# ESP32.net
KiCad netlist of a schematic drawn in Altium Designer
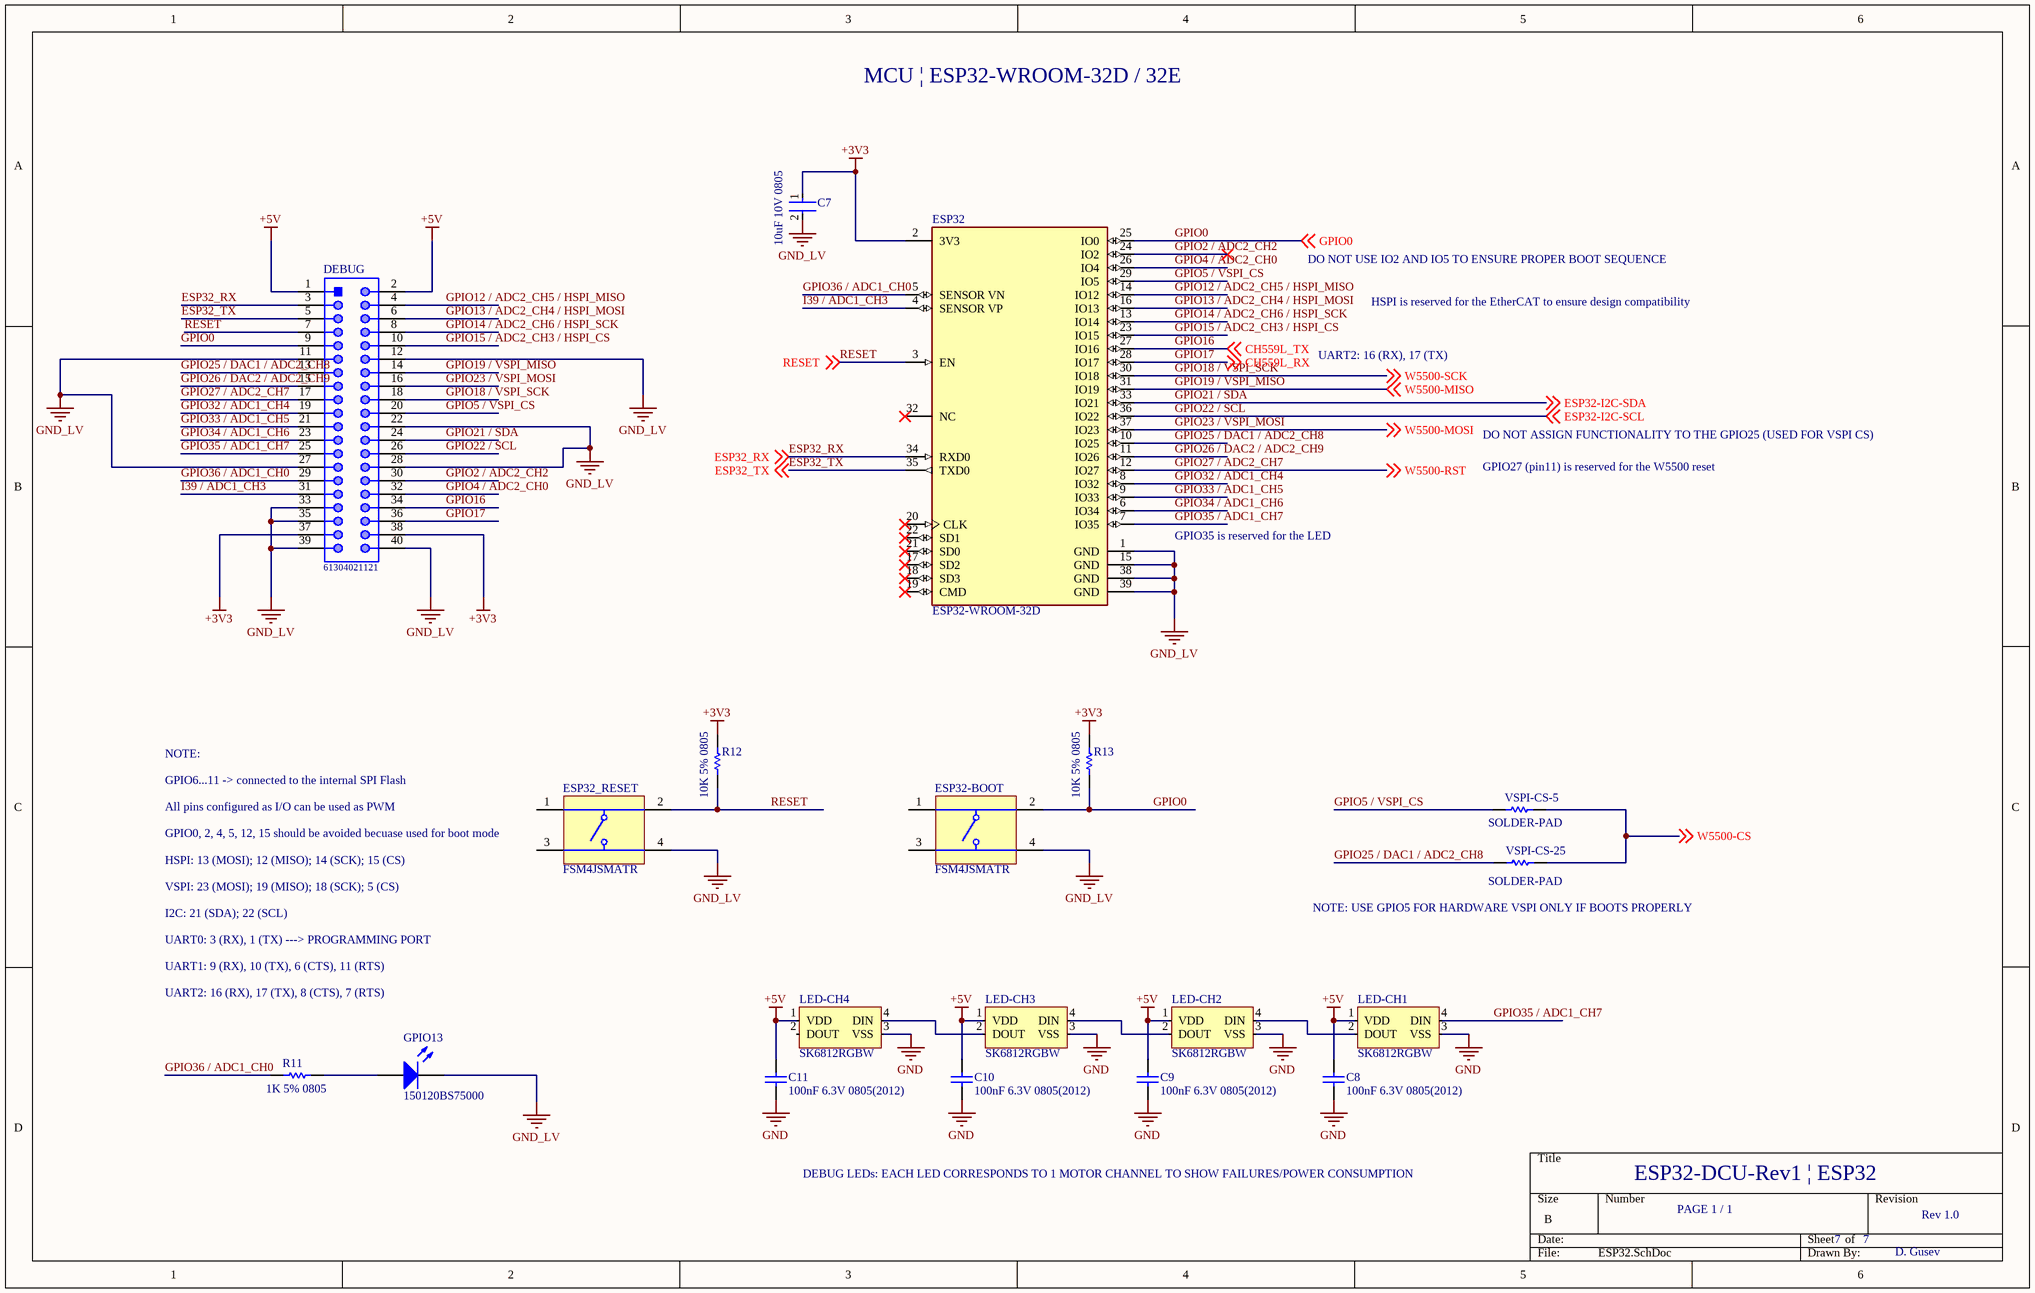
[diagram p0: ESP32.SchDoc]

(export (version "E")
  (design (tool "Eeschema 10.0.6"))
  (components
    (comp (ref "C7")
      (value "10uF 10V 0805")
      (footprint "FP-C0805C-DG-MFG")
      (description "CAP CER 10UF 10V X5R 0805")
      (fields (field (name "TOLERANCE") "10%") (field (name "MANUFACTURER PART NUMBER") "C0805C106K8PACTU"))
      (libsource (lib "Altium Content Vault") (part "11868f565c42a9108669ba33697ecf6"))
    )
    (comp (ref "C8")
      (value "100nF 6.3V 0805(2012)")
      (footprint "CAPC0805(2012)100_N")
      (description "CAP 100nF 6.3V ±20% 0805 (2012 Metric) Thickness 1mm SMD")
      (fields (field (name "TOLERANCE") "Â±20%"))
      (libsource (lib "Altium Content Vault") (part "CAP"))
    )
    (comp (ref "C9")
      (value "100nF 6.3V 0805(2012)")
      (footprint "CAPC0805(2012)100_N")
      (description "CAP 100nF 6.3V ±20% 0805 (2012 Metric) Thickness 1mm SMD")
      (fields (field (name "TOLERANCE") "Â±20%"))
      (libsource (lib "Altium Content Vault") (part "CAP"))
    )
    (comp (ref "C10")
      (value "100nF 6.3V 0805(2012)")
      (footprint "CAPC0805(2012)100_N")
      (description "CAP 100nF 6.3V ±20% 0805 (2012 Metric) Thickness 1mm SMD")
      (fields (field (name "TOLERANCE") "Â±20%"))
      (libsource (lib "Altium Content Vault") (part "CAP"))
    )
    (comp (ref "C11")
      (value "100nF 6.3V 0805(2012)")
      (footprint "CAPC0805(2012)100_N")
      (description "CAP 100nF 6.3V ±20% 0805 (2012 Metric) Thickness 1mm SMD")
      (fields (field (name "TOLERANCE") "Â±20%"))
      (libsource (lib "Altium Content Vault") (part "CAP"))
    )
    (comp (ref "DEBUG")
      (value "61304021121")
      (footprint "61304021121")
      (description "THT Vertical Pin Header WR-PHD, Pitch 2.54 mm, Dual Row, 40 pins")
      (fields (field (name "MANUFACTURER") "Wurth Elektronik") (field (name "PUBLISHER") "WurthElektronik"))
      (libsource (lib "Altium Content Vault") (part "WE-CN-2P-M-R40"))
    )
    (comp (ref "ESP32")
      (value "ESP32-WROOM-32D")
      (footprint "FP-ESP32-WROOM-32D-MFG")
      (description "WIFI MODULE 32MBITS SPI FLASH")
      (fields
        (field (name "OCTOPART") "https://octopart.com/esp32-wroom-32d-espressif+systems-91040050")
        (field (name "MANUFACTURER") "Espressif Systems")
      )
      (libsource (lib "Altium Content Vault") (part "a031a76f8c27026a7a7f4657ff233a3"))
    )
    (comp (ref "ESP32-BOOT")
      (value "FSM4JSMATR")
      (footprint "TECO-FSM4JSMATR_V")
      (description "Micro Miniature Push Button Switch FSM JSM, 50 mA, -35 to 85 degC, 4-Pin SMD, RoHS, Tape and Reel")
      (fields (field (name "MANUFACTURER") "TE Connectivity"))
      (libsource (lib "Altium Content Vault") (part "SW-SPST-4_A"))
    )
    (comp (ref "ESP32_RESET")
      (value "FSM4JSMATR")
      (footprint "TECO-FSM4JSMATR_V")
      (description "Micro Miniature Push Button Switch FSM JSM, 50 mA, -35 to 85 degC, 4-Pin SMD, RoHS, Tape and Reel")
      (fields (field (name "MANUFACTURER") "TE Connectivity"))
      (libsource (lib "Altium Content Vault") (part "SW-SPST-4_A"))
    )
    (comp (ref "GPIO13")
      (value "150120BS75000")
      (footprint "1206_A")
      (description "SMD mono-color Chip LED, WL-SMCW, Blue")
      (fields (field (name "MANUFACTURER") "Wuerth Elektronik"))
      (libsource (lib "Altium Content Vault") (part "WE-LED_K1A2-2"))
    )
    (comp (ref "LED-CH1")
      (value "SK6812RGBW")
      (footprint "SK6812RGBW")
      (libsource (lib "GT_YuYu") (part "SK6812RGBW"))
    )
    (comp (ref "LED-CH2")
      (value "SK6812RGBW")
      (footprint "SK6812RGBW")
      (libsource (lib "GT_YuYu") (part "SK6812RGBW"))
    )
    (comp (ref "LED-CH3")
      (value "SK6812RGBW")
      (footprint "SK6812RGBW")
      (libsource (lib "GT_YuYu") (part "SK6812RGBW"))
    )
    (comp (ref "LED-CH4")
      (value "SK6812RGBW")
      (footprint "SK6812RGBW")
      (libsource (lib "GT_YuYu") (part "SK6812RGBW"))
    )
    (comp (ref "R11")
      (value "1K 5% 0805")
      (footprint "RESC2013X60X40ML20T25")
      (fields (field (name "PART NUMBER") "ERA6AEB123V") (field (name "MANUFACTURER") "Panasonic"))
      (libsource (lib "Altium Content Vault") (part "RES"))
    )
    (comp (ref "R12")
      (value "10K 5% 0805")
      (footprint "RESC2013X60X40ML20T25")
      (fields (field (name "PART NUMBER") "ERA6AEB123V") (field (name "MANUFACTURER") "Panasonic"))
      (libsource (lib "Altium Content Vault") (part "RES"))
    )
    (comp (ref "R13")
      (value "10K 5% 0805")
      (footprint "RESC2013X60X40ML20T25")
      (fields (field (name "PART NUMBER") "ERA6AEB123V") (field (name "MANUFACTURER") "Panasonic"))
      (libsource (lib "Altium Content Vault") (part "RES"))
    )
    (comp (ref "VSPI-CS-5")
      (value "SOLDER-PAD")
      (footprint "RESC2013X60X35LL10T20")
      (description "Chip Resistor, 1 Ohm, +/- 1%, 125 mW, -55 to 155 degC, 0805 (2012 Metric), RoHS, Tape and Reel")
      (fields (field (name "MANUFACTURER") "Yageo"))
      (libsource (lib "Altium Content Vault") (part "RES-2"))
    )
    (comp (ref "VSPI-CS-25")
      (value "SOLDER-PAD")
      (footprint "RESC2013X60X35LL10T20")
      (description "Chip Resistor, 1 Ohm, +/- 1%, 125 mW, -55 to 155 degC, 0805 (2012 Metric), RoHS, Tape and Reel")
      (fields (field (name "MANUFACTURER") "Yageo"))
      (libsource (lib "Altium Content Vault") (part "RES-2"))
    )
  )
  (nets
    (net (code "1") (name "+3V3") (class "Default")
      (node (ref "C7") (pin "1") (pinfunction "1_1") (pintype "passive"))
      (node (ref "DEBUG") (pin "37") (pinfunction "37_37") (pintype "passive"))
      (node (ref "DEBUG") (pin "38") (pinfunction "38_38") (pintype "passive"))
      (node (ref "ESP32") (pin "2") (pinfunction "3V3_2") (pintype "power_in"))
      (node (ref "R12") (pin "2") (pinfunction "2_2") (pintype "passive"))
      (node (ref "R13") (pin "2") (pinfunction "2_2") (pintype "passive"))
    )
    (net (code "2") (name "+5V") (class "Default")
      (node (ref "C10") (pin "2") (pinfunction "2_2") (pintype "passive"))
      (node (ref "C11") (pin "2") (pinfunction "2_2") (pintype "passive"))
      (node (ref "C8") (pin "2") (pinfunction "2_2") (pintype "passive"))
      (node (ref "C9") (pin "2") (pinfunction "2_2") (pintype "passive"))
      (node (ref "DEBUG") (pin "1") (pinfunction "1_1") (pintype "passive"))
      (node (ref "DEBUG") (pin "2") (pinfunction "2_2") (pintype "passive"))
      (node (ref "LED-CH1") (pin "1") (pinfunction "VDD_1") (pintype "power_in"))
      (node (ref "LED-CH2") (pin "1") (pinfunction "VDD_1") (pintype "power_in"))
      (node (ref "LED-CH3") (pin "1") (pinfunction "VDD_1") (pintype "power_in"))
      (node (ref "LED-CH4") (pin "1") (pinfunction "VDD_1") (pintype "power_in"))
    )
    (net (code "3") (name "/GPIO2 {slash} ADC2_CH2") (class "Default")
      (node (ref "DEBUG") (pin "30") (pinfunction "30_30") (pintype "passive"))
      (node (ref "ESP32") (pin "24") (pinfunction "IO2_24") (pintype "bidirectional"))
    )
    (net (code "4") (name "/GPIO4 {slash} ADC2_CH0") (class "Default")
      (node (ref "DEBUG") (pin "32") (pinfunction "32_32") (pintype "passive"))
      (node (ref "ESP32") (pin "26") (pinfunction "IO4_26") (pintype "bidirectional"))
    )
    (net (code "5") (name "/GPIO5 {slash} VSPI_CS") (class "Default")
      (node (ref "DEBUG") (pin "20") (pinfunction "20_20") (pintype "passive"))
      (node (ref "ESP32") (pin "29") (pinfunction "IO5_29") (pintype "bidirectional"))
      (node (ref "VSPI-CS-5") (pin "1") (pinfunction "1_1") (pintype "passive"))
    )
    (net (code "6") (name "/GPIO12 {slash} ADC2_CH5 {slash} HSPI_MISO") (class "Default")
      (node (ref "DEBUG") (pin "4") (pinfunction "4_4") (pintype "passive"))
      (node (ref "ESP32") (pin "14") (pinfunction "IO12_14") (pintype "bidirectional"))
    )
    (net (code "7") (name "/GPIO13 {slash} ADC2_CH4 {slash} HSPI_MOSI") (class "Default")
      (node (ref "DEBUG") (pin "6") (pinfunction "6_6") (pintype "passive"))
      (node (ref "ESP32") (pin "16") (pinfunction "IO13_16") (pintype "bidirectional"))
    )
    (net (code "8") (name "/GPIO14 {slash} ADC2_CH6 {slash} HSPI_SCK") (class "Default")
      (node (ref "DEBUG") (pin "8") (pinfunction "8_8") (pintype "passive"))
      (node (ref "ESP32") (pin "13") (pinfunction "IO14_13") (pintype "bidirectional"))
    )
    (net (code "9") (name "/GPIO15 {slash} ADC2_CH3 {slash} HSPI_CS") (class "Default")
      (node (ref "DEBUG") (pin "10") (pinfunction "10_10") (pintype "passive"))
      (node (ref "ESP32") (pin "23") (pinfunction "IO15_23") (pintype "bidirectional"))
    )
    (net (code "10") (name "/GPIO25 {slash} DAC1 {slash} ADC2_CH8") (class "Default")
      (node (ref "DEBUG") (pin "13") (pinfunction "13_13") (pintype "passive"))
      (node (ref "ESP32") (pin "10") (pinfunction "IO25_10") (pintype "bidirectional"))
      (node (ref "VSPI-CS-25") (pin "1") (pinfunction "1_1") (pintype "passive"))
    )
    (net (code "11") (name "/GPIO26 {slash} DAC2 {slash} ADC2_CH9") (class "Default")
      (node (ref "DEBUG") (pin "15") (pinfunction "15_15") (pintype "passive"))
      (node (ref "ESP32") (pin "11") (pinfunction "IO26_11") (pintype "bidirectional"))
    )
    (net (code "12") (name "/GPIO32 {slash} ADC1_CH4") (class "Default")
      (node (ref "DEBUG") (pin "19") (pinfunction "19_19") (pintype "passive"))
      (node (ref "ESP32") (pin "8") (pinfunction "IO32_8") (pintype "bidirectional"))
    )
    (net (code "13") (name "/GPIO33 {slash} ADC1_CH5") (class "Default")
      (node (ref "DEBUG") (pin "21") (pinfunction "21_21") (pintype "passive"))
      (node (ref "ESP32") (pin "9") (pinfunction "IO33_9") (pintype "bidirectional"))
    )
    (net (code "14") (name "/GPIO34 {slash} ADC1_CH6") (class "Default")
      (node (ref "DEBUG") (pin "23") (pinfunction "23_23") (pintype "passive"))
      (node (ref "ESP32") (pin "6") (pinfunction "IO34_6") (pintype "bidirectional"))
    )
    (net (code "15") (name "/GPIO35 {slash} ADC1_CH7") (class "Default")
      (node (ref "DEBUG") (pin "25") (pinfunction "25_25") (pintype "passive"))
      (node (ref "ESP32") (pin "7") (pinfunction "IO35_7") (pintype "bidirectional"))
      (node (ref "LED-CH1") (pin "4") (pinfunction "DIN_4") (pintype "input"))
    )
    (net (code "16") (name "/GPIO36 {slash} ADC1_CH0") (class "Default")
      (node (ref "DEBUG") (pin "29") (pinfunction "29_29") (pintype "passive"))
      (node (ref "ESP32") (pin "5") (pinfunction "SENSOR_VN_5") (pintype "bidirectional"))
      (node (ref "R11") (pin "1") (pinfunction "1_1") (pintype "passive"))
    )
    (net (code "17") (name "/I39 {slash} ADC1_CH3") (class "Default")
      (node (ref "DEBUG") (pin "31") (pinfunction "31_31") (pintype "passive"))
      (node (ref "ESP32") (pin "4") (pinfunction "SENSOR_VP_4") (pintype "bidirectional"))
    )
    (net (code "18") (name "CH559L_RX") (class "Default")
      (node (ref "DEBUG") (pin "36") (pinfunction "36_36") (pintype "passive"))
      (node (ref "ESP32") (pin "28") (pinfunction "IO17_28") (pintype "bidirectional"))
    )
    (net (code "19") (name "CH559L_TX") (class "Default")
      (node (ref "DEBUG") (pin "34") (pinfunction "34_34") (pintype "passive"))
      (node (ref "ESP32") (pin "27") (pinfunction "IO16_27") (pintype "bidirectional"))
    )
    (net (code "20") (name "ESP32-I2C-SCL") (class "Default")
      (node (ref "DEBUG") (pin "26") (pinfunction "26_26") (pintype "passive"))
      (node (ref "ESP32") (pin "36") (pinfunction "IO22_36") (pintype "bidirectional"))
    )
    (net (code "21") (name "ESP32-I2C-SDA") (class "Default")
      (node (ref "DEBUG") (pin "24") (pinfunction "24_24") (pintype "passive"))
      (node (ref "ESP32") (pin "33") (pinfunction "IO21_33") (pintype "bidirectional"))
    )
    (net (code "22") (name "ESP32_RX") (class "Default")
      (node (ref "DEBUG") (pin "3") (pinfunction "3_3") (pintype "passive"))
      (node (ref "ESP32") (pin "34") (pinfunction "RXD0_34") (pintype "input"))
    )
    (net (code "23") (name "ESP32_TX") (class "Default")
      (node (ref "DEBUG") (pin "5") (pinfunction "5_5") (pintype "passive"))
      (node (ref "ESP32") (pin "35") (pinfunction "TXD0_35") (pintype "output"))
    )
    (net (code "24") (name "GND") (class "Default")
      (node (ref "C10") (pin "1") (pinfunction "1_1") (pintype "passive"))
      (node (ref "C11") (pin "1") (pinfunction "1_1") (pintype "passive"))
      (node (ref "C8") (pin "1") (pinfunction "1_1") (pintype "passive"))
      (node (ref "C9") (pin "1") (pinfunction "1_1") (pintype "passive"))
      (node (ref "LED-CH1") (pin "3") (pinfunction "VSS_3") (pintype "power_in"))
      (node (ref "LED-CH2") (pin "3") (pinfunction "VSS_3") (pintype "power_in"))
      (node (ref "LED-CH3") (pin "3") (pinfunction "VSS_3") (pintype "power_in"))
      (node (ref "LED-CH4") (pin "3") (pinfunction "VSS_3") (pintype "power_in"))
    )
    (net (code "25") (name "GND_LV") (class "Default")
      (node (ref "C7") (pin "2") (pinfunction "2_2") (pintype "passive"))
      (node (ref "DEBUG") (pin "11") (pinfunction "11_11") (pintype "passive"))
      (node (ref "DEBUG") (pin "12") (pinfunction "12_12") (pintype "passive"))
      (node (ref "DEBUG") (pin "22") (pinfunction "22_22") (pintype "passive"))
      (node (ref "DEBUG") (pin "27") (pinfunction "27_27") (pintype "passive"))
      (node (ref "DEBUG") (pin "28") (pinfunction "28_28") (pintype "passive"))
      (node (ref "DEBUG") (pin "33") (pinfunction "33_33") (pintype "passive"))
      (node (ref "DEBUG") (pin "35") (pinfunction "35_35") (pintype "passive"))
      (node (ref "DEBUG") (pin "39") (pinfunction "39_39") (pintype "passive"))
      (node (ref "DEBUG") (pin "40") (pinfunction "40_40") (pintype "passive"))
      (node (ref "ESP32") (pin "1") (pinfunction "GND_1") (pintype "power_in"))
      (node (ref "ESP32") (pin "15") (pinfunction "GND_15") (pintype "power_in"))
      (node (ref "ESP32") (pin "38") (pinfunction "GND_38") (pintype "power_in"))
      (node (ref "ESP32") (pin "39") (pinfunction "GND_39") (pintype "power_in"))
      (node (ref "ESP32-BOOT") (pin "4") (pinfunction "4_4") (pintype "passive"))
      (node (ref "ESP32_RESET") (pin "4") (pinfunction "4_4") (pintype "passive"))
      (node (ref "GPIO13") (pin "1") (pinfunction "K_1") (pintype "passive"))
    )
    (net (code "26") (name "GPIO0") (class "Default")
      (node (ref "DEBUG") (pin "9") (pinfunction "9_9") (pintype "passive"))
      (node (ref "ESP32") (pin "25") (pinfunction "IO0_25") (pintype "bidirectional"))
      (node (ref "ESP32-BOOT") (pin "2") (pinfunction "2_2") (pintype "passive"))
      (node (ref "R13") (pin "1") (pinfunction "1_1") (pintype "passive"))
    )
    (net (code "27") (name "Net-(GPIO13-A)") (class "Default")
      (node (ref "GPIO13") (pin "2") (pinfunction "A_2") (pintype "passive"))
      (node (ref "R11") (pin "2") (pinfunction "2_2") (pintype "passive"))
    )
    (net (code "28") (name "Net-(LED-CH1-DOUT)") (class "Default")
      (node (ref "LED-CH1") (pin "2") (pinfunction "DOUT_2") (pintype "output"))
      (node (ref "LED-CH2") (pin "4") (pinfunction "DIN_4") (pintype "input"))
    )
    (net (code "29") (name "Net-(LED-CH2-DOUT)") (class "Default")
      (node (ref "LED-CH2") (pin "2") (pinfunction "DOUT_2") (pintype "output"))
      (node (ref "LED-CH3") (pin "4") (pinfunction "DIN_4") (pintype "input"))
    )
    (net (code "30") (name "Net-(LED-CH3-DOUT)") (class "Default")
      (node (ref "LED-CH3") (pin "2") (pinfunction "DOUT_2") (pintype "output"))
      (node (ref "LED-CH4") (pin "4") (pinfunction "DIN_4") (pintype "input"))
    )
    (net (code "31") (name "RESET") (class "Default")
      (node (ref "DEBUG") (pin "7") (pinfunction "7_7") (pintype "passive"))
      (node (ref "ESP32") (pin "3") (pinfunction "EN_3") (pintype "input"))
      (node (ref "ESP32_RESET") (pin "2") (pinfunction "2_2") (pintype "passive"))
      (node (ref "R12") (pin "1") (pinfunction "1_1") (pintype "passive"))
    )
    (net (code "32") (name "W5500-CS") (class "Default")
      (node (ref "VSPI-CS-25") (pin "2") (pinfunction "2_2") (pintype "passive"))
      (node (ref "VSPI-CS-5") (pin "2") (pinfunction "2_2") (pintype "passive"))
    )
    (net (code "33") (name "W5500-MISO") (class "Default")
      (node (ref "DEBUG") (pin "14") (pinfunction "14_14") (pintype "passive"))
      (node (ref "ESP32") (pin "31") (pinfunction "IO19_31") (pintype "bidirectional"))
    )
    (net (code "34") (name "W5500-MOSI") (class "Default")
      (node (ref "DEBUG") (pin "16") (pinfunction "16_16") (pintype "passive"))
      (node (ref "ESP32") (pin "37") (pinfunction "IO23_37") (pintype "bidirectional"))
    )
    (net (code "35") (name "W5500-RST") (class "Default")
      (node (ref "DEBUG") (pin "17") (pinfunction "17_17") (pintype "passive"))
      (node (ref "ESP32") (pin "12") (pinfunction "IO27_12") (pintype "bidirectional"))
    )
    (net (code "36") (name "W5500-SCK") (class "Default")
      (node (ref "DEBUG") (pin "18") (pinfunction "18_18") (pintype "passive"))
      (node (ref "ESP32") (pin "30") (pinfunction "IO18_30") (pintype "bidirectional"))
    )
    (net (code "37") (name "unconnected-(ESP32-BOOT-Pad1)") (class "Default")
      (node (ref "ESP32-BOOT") (pin "1") (pinfunction "1_1") (pintype "passive"))
    )
    (net (code "38") (name "unconnected-(ESP32-BOOT-Pad3)") (class "Default")
      (node (ref "ESP32-BOOT") (pin "3") (pinfunction "3_3") (pintype "passive"))
    )
    (net (code "39") (name "unconnected-(ESP32-CLK-Pad20)") (class "Default")
      (node (ref "ESP32") (pin "20") (pinfunction "CLK_20") (pintype "input+no_connect"))
    )
    (net (code "40") (name "unconnected-(ESP32-CMD-Pad19)") (class "Default")
      (node (ref "ESP32") (pin "19") (pinfunction "CMD_19") (pintype "bidirectional+no_connect"))
    )
    (net (code "41") (name "unconnected-(ESP32-NC-Pad32)") (class "Default")
      (node (ref "ESP32") (pin "32") (pinfunction "NC_32") (pintype "passive+no_connect"))
    )
    (net (code "42") (name "unconnected-(ESP32-SD0-Pad21)") (class "Default")
      (node (ref "ESP32") (pin "21") (pinfunction "SD0_21") (pintype "bidirectional+no_connect"))
    )
    (net (code "43") (name "unconnected-(ESP32-SD1-Pad22)") (class "Default")
      (node (ref "ESP32") (pin "22") (pinfunction "SD1_22") (pintype "bidirectional+no_connect"))
    )
    (net (code "44") (name "unconnected-(ESP32-SD2-Pad17)") (class "Default")
      (node (ref "ESP32") (pin "17") (pinfunction "SD2_17") (pintype "bidirectional+no_connect"))
    )
    (net (code "45") (name "unconnected-(ESP32-SD3-Pad18)") (class "Default")
      (node (ref "ESP32") (pin "18") (pinfunction "SD3_18") (pintype "bidirectional+no_connect"))
    )
    (net (code "46") (name "unconnected-(ESP32_RESET-Pad1)") (class "Default")
      (node (ref "ESP32_RESET") (pin "1") (pinfunction "1_1") (pintype "passive"))
    )
    (net (code "47") (name "unconnected-(ESP32_RESET-Pad3)") (class "Default")
      (node (ref "ESP32_RESET") (pin "3") (pinfunction "3_3") (pintype "passive"))
    )
    (net (code "48") (name "unconnected-(LED-CH4-DOUT-Pad2)") (class "Default")
      (node (ref "LED-CH4") (pin "2") (pinfunction "DOUT_2") (pintype "output"))
    )
  )
)
